# lab3_task2.net
KiCad netlist of a schematic drawn in EAGLE
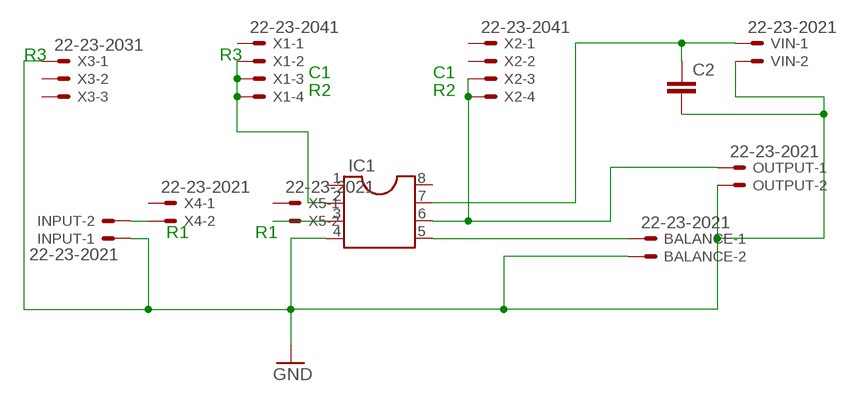
[diagram p0: schematic, sheet 1]

(export (version "E")
  (design (tool "Eeschema 10.0.6"))
  (components
    (comp (ref "BALANCE")
      (value "22-23-2021")
      (footprint "eagle-import:22-23-2021")
      (fields (field (name "MF") "MOLEX"))
      (libsource (lib "eagle-import") (part "22-23-2021"))
    )
    (comp (ref "C2")
      (value "C-EU102-064X133")
      (footprint "eagle-import:C102-064X133")
      (libsource (lib "eagle-import") (part "C-EU102-064X133"))
    )
    (comp (ref "IC1")
      (value "DIL8")
      (footprint "eagle-import:DIL08")
      (libsource (lib "eagle-import") (part "DIL8"))
    )
    (comp (ref "INPUT")
      (value "22-23-2021")
      (footprint "eagle-import:22-23-2021")
      (fields (field (name "MF") "MOLEX"))
      (libsource (lib "eagle-import") (part "22-23-2021"))
    )
    (comp (ref "OUTPUT")
      (value "22-23-2021")
      (footprint "eagle-import:22-23-2021")
      (fields (field (name "MF") "MOLEX"))
      (libsource (lib "eagle-import") (part "22-23-2021"))
    )
    (comp (ref "VIN")
      (value "22-23-2021")
      (footprint "eagle-import:22-23-2021")
      (fields (field (name "MF") "MOLEX"))
      (libsource (lib "eagle-import") (part "22-23-2021"))
    )
    (comp (ref "X1")
      (value "22-23-2041")
      (footprint "eagle-import:22-23-2041")
      (fields (field (name "MF") "MOLEX"))
      (libsource (lib "eagle-import") (part "22-23-2041"))
    )
    (comp (ref "X2")
      (value "22-23-2041")
      (footprint "eagle-import:22-23-2041")
      (fields (field (name "MF") "MOLEX"))
      (libsource (lib "eagle-import") (part "22-23-2041"))
    )
    (comp (ref "X3")
      (value "22-23-2031")
      (footprint "eagle-import:22-23-2031")
      (fields (field (name "MF") "MOLEX"))
      (libsource (lib "eagle-import") (part "22-23-2031"))
    )
    (comp (ref "X4")
      (value "22-23-2021")
      (footprint "eagle-import:22-23-2021")
      (fields (field (name "MF") "MOLEX"))
      (libsource (lib "eagle-import") (part "22-23-2021"))
    )
    (comp (ref "X5")
      (value "22-23-2021")
      (footprint "eagle-import:22-23-2021")
      (fields (field (name "MF") "MOLEX"))
      (libsource (lib "eagle-import") (part "22-23-2021"))
    )
  )
  (nets
    (net (code "1") (name "GND") (class "Default")
      (node (ref "BALANCE") (pin "2") (pinfunction "S_2") (pintype "passive"))
      (node (ref "C2") (pin "2") (pinfunction "2_2") (pintype "passive"))
      (node (ref "IC1") (pin "4") (pinfunction "4_4") (pintype "passive"))
      (node (ref "INPUT") (pin "1") (pinfunction "S_1") (pintype "passive"))
      (node (ref "OUTPUT") (pin "2") (pinfunction "S_2") (pintype "passive"))
      (node (ref "VIN") (pin "2") (pinfunction "S_2") (pintype "passive"))
      (node (ref "X3") (pin "1") (pinfunction "S_1") (pintype "passive"))
    )
    (net (code "2") (name "Net-(BALANCEA-S)") (class "Default")
      (node (ref "BALANCE") (pin "1") (pinfunction "S_1") (pintype "passive"))
      (node (ref "IC1") (pin "5") (pinfunction "5_5") (pintype "passive"))
    )
    (net (code "3") (name "Net-(INPUTB-S)") (class "Default")
      (node (ref "INPUT") (pin "2") (pinfunction "S_2") (pintype "passive"))
      (node (ref "X4") (pin "2") (pinfunction "S_2") (pintype "passive"))
    )
    (net (code "4") (name "Net-(OUTPUTA-S)") (class "Default")
      (node (ref "IC1") (pin "6") (pinfunction "6_6") (pintype "passive"))
      (node (ref "OUTPUT") (pin "1") (pinfunction "S_1") (pintype "passive"))
      (node (ref "X2") (pin "3") (pinfunction "S_3") (pintype "passive"))
      (node (ref "X2") (pin "4") (pinfunction "S_4") (pintype "passive"))
    )
    (net (code "5") (name "Net-(VINA-S)") (class "Default")
      (node (ref "C2") (pin "1") (pinfunction "1_1") (pintype "passive"))
      (node (ref "IC1") (pin "7") (pinfunction "7_7") (pintype "passive"))
      (node (ref "VIN") (pin "1") (pinfunction "S_1") (pintype "passive"))
    )
    (net (code "6") (name "Net-(X1B-S)") (class "Default")
      (node (ref "IC1") (pin "2") (pinfunction "2_2") (pintype "passive"))
      (node (ref "X1") (pin "2") (pinfunction "S_2") (pintype "passive"))
      (node (ref "X1") (pin "3") (pinfunction "S_3") (pintype "passive"))
      (node (ref "X1") (pin "4") (pinfunction "S_4") (pintype "passive"))
    )
    (net (code "7") (name "Net-(X5B-S)") (class "Default")
      (node (ref "IC1") (pin "3") (pinfunction "3_3") (pintype "passive"))
      (node (ref "X5") (pin "2") (pinfunction "S_2") (pintype "passive"))
    )
    (net (code "8") (name "unconnected-(IC1-Pad1)") (class "Default")
      (node (ref "IC1") (pin "1") (pinfunction "1_1") (pintype "passive"))
    )
    (net (code "9") (name "unconnected-(IC1-Pad8)") (class "Default")
      (node (ref "IC1") (pin "8") (pinfunction "8_8") (pintype "passive"))
    )
    (net (code "10") (name "unconnected-(X1A-S-Pad1)") (class "Default")
      (node (ref "X1") (pin "1") (pinfunction "S_1") (pintype "passive"))
    )
    (net (code "11") (name "unconnected-(X2A-S-Pad1)") (class "Default")
      (node (ref "X2") (pin "1") (pinfunction "S_1") (pintype "passive"))
    )
    (net (code "12") (name "unconnected-(X2B-S-Pad2)") (class "Default")
      (node (ref "X2") (pin "2") (pinfunction "S_2") (pintype "passive"))
    )
    (net (code "13") (name "unconnected-(X3B-S-Pad2)") (class "Default")
      (node (ref "X3") (pin "2") (pinfunction "S_2") (pintype "passive"))
    )
    (net (code "14") (name "unconnected-(X3C-S-Pad3)") (class "Default")
      (node (ref "X3") (pin "3") (pinfunction "S_3") (pintype "passive"))
    )
    (net (code "15") (name "unconnected-(X4A-S-Pad1)") (class "Default")
      (node (ref "X4") (pin "1") (pinfunction "S_1") (pintype "passive"))
    )
    (net (code "16") (name "unconnected-(X5A-S-Pad1)") (class "Default")
      (node (ref "X5") (pin "1") (pinfunction "S_1") (pintype "passive"))
    )
  )
)
